# schematic.net
KiCad netlist of a schematic drawn in Altium Designer
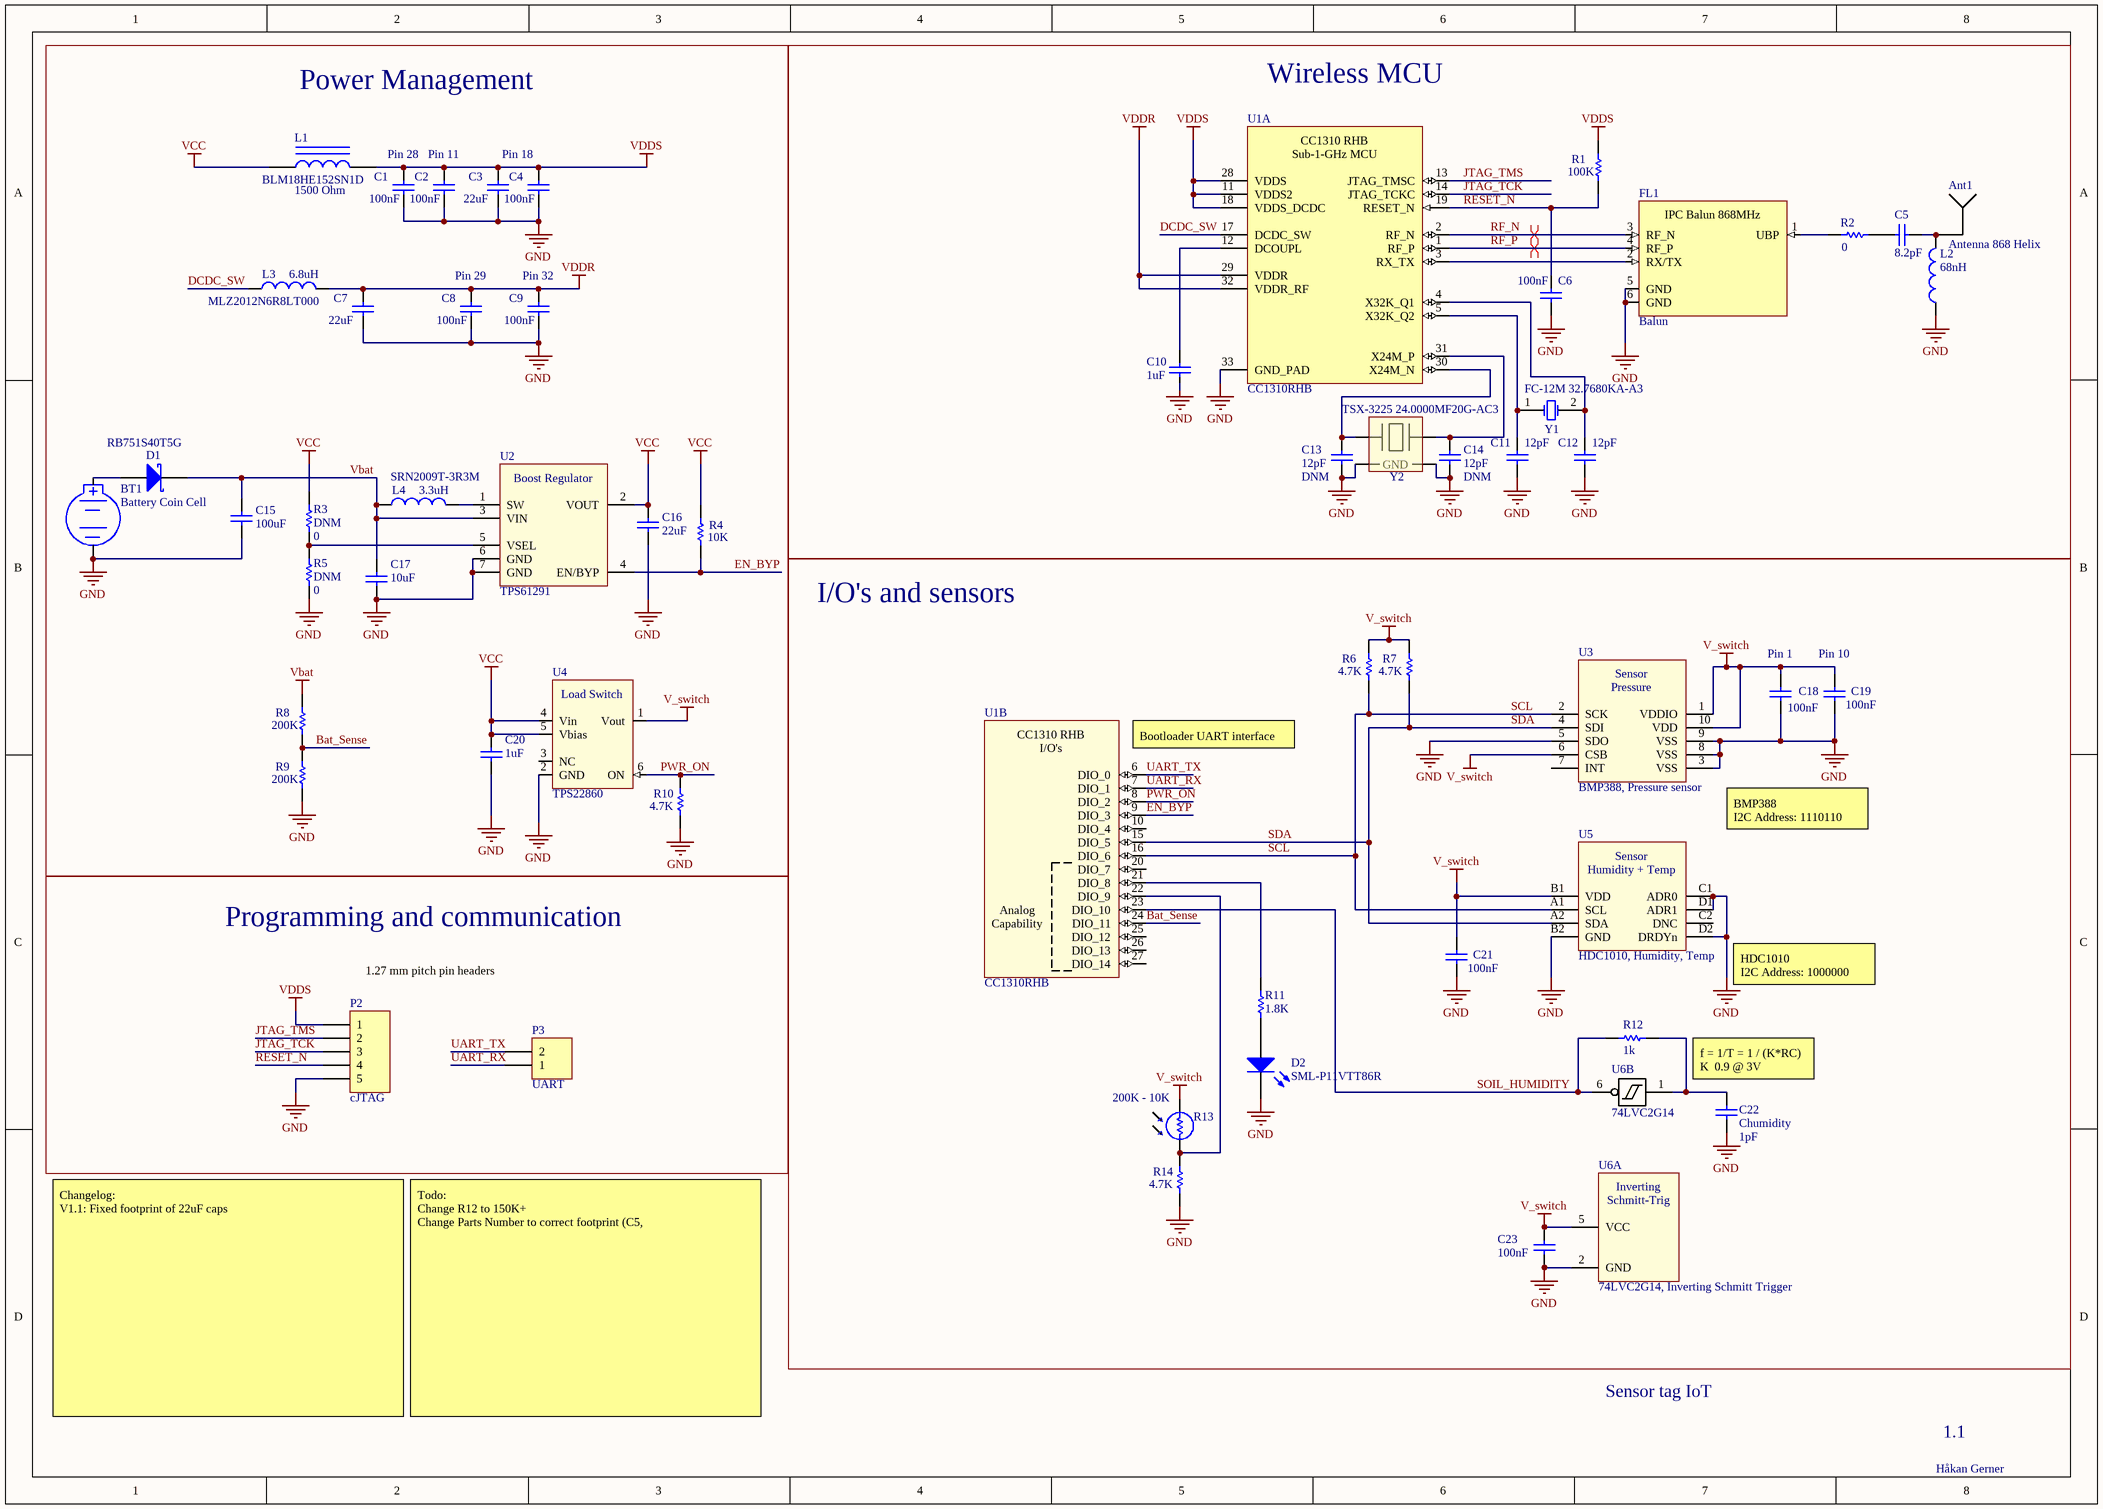
[diagram p0: schematic.SchDoc]

(export (version "E")
  (design (tool "Eeschema 10.0.6"))
  (components
    (comp (ref "Ant1")
      (value "Antenna 868 Helix")
      (footprint "Antenna_868_Helix")
      (libsource (lib "components") (part "Antenna 868 Helix"))
    )
    (comp (ref "BT1")
      (value "Battery Coin Cell")
      (footprint "S8421-45R")
      (fields (field (name "PART NUMBER") "S8421-45R"))
      (libsource (lib "components") (part "Battery Coin Cell"))
    )
    (comp (ref "C1")
      (value "100nF")
      (footprint "0402 (CAP)")
      (description "Capacitor")
      (fields
        (field (name "PART NUMBER") "GCM155R71C104KA55J")
        (field (name "Comment") "Cap")
        (field (name "PUBLISHER") "Altium Limited")
      )
      (libsource (lib "Miscellaneous Devices") (part "Cap"))
    )
    (comp (ref "C2")
      (value "100nF")
      (footprint "0402 (CAP)")
      (description "Capacitor")
      (fields
        (field (name "PART NUMBER") "GCM155R71C104KA55J")
        (field (name "Comment") "Cap")
        (field (name "PUBLISHER") "Altium Limited")
      )
      (libsource (lib "Miscellaneous Devices") (part "Cap"))
    )
    (comp (ref "C3")
      (value "22uF")
      (footprint "0603 (CAP)")
      (description "Capacitor")
      (fields
        (field (name "PART NUMBER") "GRM188R61A226ME15D")
        (field (name "Comment") "Cap")
        (field (name "PUBLISHER") "Altium Limited")
      )
      (libsource (lib "Miscellaneous Devices") (part "Cap"))
    )
    (comp (ref "C4")
      (value "100nF")
      (footprint "0402 (CAP)")
      (description "Capacitor")
      (fields
        (field (name "PART NUMBER") "GCM155R71C104KA55J")
        (field (name "Comment") "Cap")
        (field (name "PUBLISHER") "Altium Limited")
      )
      (libsource (lib "Miscellaneous Devices") (part "Cap"))
    )
    (comp (ref "C5")
      (value "8.2pF")
      (footprint "0402 (CAP)")
      (description "Capacitor")
      (fields
        (field (name "PART NUMBER") "250R05L8R2CV4T")
        (field (name "Comment") "Cap")
        (field (name "PUBLISHER") "Altium Limited")
      )
      (libsource (lib "Miscellaneous Devices") (part "Cap"))
    )
    (comp (ref "C6")
      (value "100nF")
      (footprint "0402 (CAP)")
      (description "Capacitor")
      (fields
        (field (name "PART NUMBER") "GCM155R71C104KA55J")
        (field (name "Comment") "Cap")
        (field (name "PUBLISHER") "Altium Limited")
      )
      (libsource (lib "Miscellaneous Devices") (part "Cap"))
    )
    (comp (ref "C7")
      (value "22uF")
      (footprint "0603 (CAP)")
      (description "Capacitor")
      (fields
        (field (name "PART NUMBER") "GRM188R61A226ME15D")
        (field (name "Comment") "Cap")
        (field (name "PUBLISHER") "Altium Limited")
      )
      (libsource (lib "Miscellaneous Devices") (part "Cap"))
    )
    (comp (ref "C8")
      (value "100nF")
      (footprint "0402 (CAP)")
      (description "Capacitor")
      (fields
        (field (name "PART NUMBER") "GCM155R71C104KA55J")
        (field (name "Comment") "Cap")
        (field (name "PUBLISHER") "Altium Limited")
      )
      (libsource (lib "Miscellaneous Devices") (part "Cap"))
    )
    (comp (ref "C9")
      (value "100nF")
      (footprint "0402 (CAP)")
      (description "Capacitor")
      (fields
        (field (name "PART NUMBER") "GCM155R71C104KA55J")
        (field (name "Comment") "Cap")
        (field (name "PUBLISHER") "Altium Limited")
      )
      (libsource (lib "Miscellaneous Devices") (part "Cap"))
    )
    (comp (ref "C10")
      (value "1uF")
      (footprint "0603 (CAP)")
      (description "Capacitor")
      (fields
        (field (name "PART NUMBER") "GCM188R71E105KA64D")
        (field (name "Comment") "Cap")
        (field (name "PUBLISHER") "Altium Limited")
      )
      (libsource (lib "Miscellaneous Devices") (part "Cap"))
    )
    (comp (ref "C11")
      (value "12pF")
      (footprint "0402 (CAP)")
      (description "Capacitor")
      (fields
        (field (name "PART NUMBER") "GCM1555C1H120JA16D")
        (field (name "Comment") "Cap")
        (field (name "PUBLISHER") "Altium Limited")
      )
      (libsource (lib "Miscellaneous Devices") (part "Cap"))
    )
    (comp (ref "C12")
      (value "12pF")
      (footprint "0402 (CAP)")
      (description "Capacitor")
      (fields
        (field (name "PART NUMBER") "GCM1555C1H120JA16D")
        (field (name "Comment") "Cap")
        (field (name "PUBLISHER") "Altium Limited")
      )
      (libsource (lib "Miscellaneous Devices") (part "Cap"))
    )
    (comp (ref "C13")
      (value "DNM")
      (footprint "0402 (CAP)")
      (description "Capacitor")
      (fields
        (field (name "ALTIUM_VALUE") "12pF")
        (field (name "PART NUMBER") "GCM1555C1H120JA16D")
        (field (name "PUBLISHER") "Altium Limited")
      )
      (libsource (lib "Miscellaneous Devices") (part "Cap"))
    )
    (comp (ref "C14")
      (value "DNM")
      (footprint "0402 (CAP)")
      (description "Capacitor")
      (fields
        (field (name "ALTIUM_VALUE") "12pF")
        (field (name "PART NUMBER") "GCM1555C1H120JA16D")
        (field (name "PUBLISHER") "Altium Limited")
      )
      (libsource (lib "Miscellaneous Devices") (part "Cap"))
    )
    (comp (ref "C15")
      (value "100uF")
      (footprint "1210 (CAP)")
      (description "Capacitor")
      (fields
        (field (name "PART NUMBER") "GCM155R71C104KA55J")
        (field (name "Comment") "GRM32EC70J107ME15L")
        (field (name "PUBLISHER") "Altium Limited")
      )
      (libsource (lib "Miscellaneous Devices") (part "Cap"))
    )
    (comp (ref "C16")
      (value "22uF")
      (footprint "0805 (CAP)")
      (description "Capacitor")
      (fields
        (field (name "PART NUMBER") "GRM21BD71A226ME44L")
        (field (name "Comment") "Cap")
        (field (name "PUBLISHER") "Altium Limited")
      )
      (libsource (lib "Miscellaneous Devices") (part "Cap"))
    )
    (comp (ref "C17")
      (value "10uF")
      (footprint "0805 (CAP)")
      (description "Capacitor")
      (fields
        (field (name "PART NUMBER") "GRM21BC71C106KE11L")
        (field (name "Comment") "Cap")
        (field (name "PUBLISHER") "Altium Limited")
      )
      (libsource (lib "Miscellaneous Devices") (part "Cap"))
    )
    (comp (ref "C18")
      (value "100nF")
      (footprint "0402 (CAP)")
      (description "Capacitor")
      (fields
        (field (name "PART NUMBER") "GCM155R71C104KA55J")
        (field (name "Comment") "Cap")
        (field (name "PUBLISHER") "Altium Limited")
      )
      (libsource (lib "Miscellaneous Devices") (part "Cap"))
    )
    (comp (ref "C19")
      (value "100nF")
      (footprint "0402 (CAP)")
      (description "Capacitor")
      (fields
        (field (name "PART NUMBER") "GCM155R71C104KA55J")
        (field (name "Comment") "Cap")
        (field (name "PUBLISHER") "Altium Limited")
      )
      (libsource (lib "Miscellaneous Devices") (part "Cap"))
    )
    (comp (ref "C20")
      (value "1uF")
      (footprint "0603 (CAP)")
      (description "Capacitor")
      (fields
        (field (name "PART NUMBER") "GCM188R71E105KA64D")
        (field (name "Comment") "Cap")
        (field (name "PUBLISHER") "Altium Limited")
      )
      (libsource (lib "Miscellaneous Devices") (part "Cap"))
    )
    (comp (ref "C21")
      (value "100nF")
      (footprint "0402 (CAP)")
      (description "Capacitor")
      (fields
        (field (name "PART NUMBER") "GCM155R71C104KA55J")
        (field (name "Comment") "Cap")
        (field (name "PUBLISHER") "Altium Limited")
      )
      (libsource (lib "Miscellaneous Devices") (part "Cap"))
    )
    (comp (ref "C22")
      (value "Chumidity")
      (footprint "Soil_Cap")
      (description "Capacitor")
      (fields (field (name "ALTIUM_VALUE") "1pF") (field (name "PUBLISHER") "Altium Limited"))
      (libsource (lib "Miscellaneous Devices") (part "Cap"))
    )
    (comp (ref "C23")
      (value "100nF")
      (footprint "0402 (CAP)")
      (description "Capacitor")
      (fields
        (field (name "PART NUMBER") "GCM155R71C104KA55J")
        (field (name "Comment") "Cap")
        (field (name "PUBLISHER") "Altium Limited")
      )
      (libsource (lib "Miscellaneous Devices") (part "Cap"))
    )
    (comp (ref "D1")
      (value "RB751S40T5G")
      (footprint "SOD-523")
      (description "Schottky Diode")
      (fields (field (name "PUBLISHER") "Altium Limited"))
      (libsource (lib "Miscellaneous Devices") (part "D Schottky"))
    )
    (comp (ref "D2")
      (value "SML-P11VTT86R")
      (footprint "0402 (RES)")
      (description "Typical RED, GREEN, YELLOW, AMBER GaAs LED")
      (fields (field (name "PUBLISHER") "Altium Limited"))
      (libsource (lib "Miscellaneous Devices") (part "LED2"))
    )
    (comp (ref "FL1")
      (value "Balun")
      (footprint "0850BM14E0016")
      (fields (field (name "PART NUMBER") "0850BM14E0016T"))
      (libsource (lib "components") (part "0850BM14E0016"))
    )
    (comp (ref "L1")
      (value "BLM18HE152SN1D")
      (footprint "0603 (IND)")
      (description "Magnetic-Core Inductor")
      (fields (field (name "ALTIUM_VALUE") "1500 Ohm") (field (name "PUBLISHER") "Altium Limited"))
      (libsource (lib "Miscellaneous Devices") (part "Inductor Iron"))
    )
    (comp (ref "L2")
      (value "68nH")
      (footprint "0603 (IND)")
      (description "Inductor")
      (fields (field (name "PART NUMBER") "PE-0603CD680GTT") (field (name "PUBLISHER") "Altium Limited"))
      (libsource (lib "") (part "Inductor_1"))
    )
    (comp (ref "L3")
      (value "MLZ2012N6R8LT000")
      (footprint "0805 (IND)")
      (description "Inductor")
      (fields (field (name "ALTIUM_VALUE") "6.8uH") (field (name "PUBLISHER") "Altium Limited"))
      (libsource (lib "Miscellaneous Devices") (part "Inductor"))
    )
    (comp (ref "L4")
      (value "3.3uH")
      (footprint "SRN2009T")
      (description "Inductor")
      (fields (field (name "PART NUMBER") "SRN2009T-3R3M") (field (name "PUBLISHER") "Altium Limited"))
      (libsource (lib "Miscellaneous Devices") (part "Inductor"))
    )
    (comp (ref "P2")
      (value "cJTAG")
      (footprint "5pin-1.27")
      (description "Header, 5-Pin")
      (fields (field (name "PUBLISHER") "Altium Limited"))
      (libsource (lib "Miscellaneous Connectors") (part "Header 5"))
    )
    (comp (ref "P3")
      (value "UART")
      (footprint "2pin-1.27")
      (description "Header, 2-Pin")
      (fields (field (name "PUBLISHER") "Altium Limited"))
      (libsource (lib "Miscellaneous Connectors") (part "Header 2"))
    )
    (comp (ref "R1")
      (value "100K")
      (footprint "0402 (RES)")
      (description "Resistor")
      (fields
        (field (name "PART NUMBER") "CRCW0402100KFKED")
        (field (name "Comment") "Res1")
        (field (name "PUBLISHER") "Altium Limited")
      )
      (libsource (lib "Miscellaneous Devices") (part "Res1"))
    )
    (comp (ref "R2")
      (value "0")
      (footprint "0402 (RES)")
      (description "Resistor")
      (fields (field (name "PART NUMBER") "ERJ-2GE0R00X") (field (name "PUBLISHER") "Altium Limited"))
      (libsource (lib "Miscellaneous Devices") (part "Res1"))
    )
    (comp (ref "R3")
      (value "DNM")
      (footprint "0402 (RES)")
      (description "Resistor")
      (fields
        (field (name "ALTIUM_VALUE") "0")
        (field (name "PART NUMBER") "ERJ-2GE0R00X")
        (field (name "PUBLISHER") "Altium Limited")
      )
      (libsource (lib "Miscellaneous Devices") (part "Res1"))
    )
    (comp (ref "R4")
      (value "10K")
      (footprint "0402 (RES)")
      (description "Resistor")
      (fields
        (field (name "PART NUMBER") "CRCW040210K0JNEDC")
        (field (name "Comment") "Res1")
        (field (name "PUBLISHER") "Altium Limited")
      )
      (libsource (lib "Miscellaneous Devices") (part "Res1"))
    )
    (comp (ref "R5")
      (value "DNM")
      (footprint "0402 (RES)")
      (description "Resistor")
      (fields
        (field (name "ALTIUM_VALUE") "0")
        (field (name "PART NUMBER") "ERJ-2GE0R00X")
        (field (name "PUBLISHER") "Altium Limited")
      )
      (libsource (lib "Miscellaneous Devices") (part "Res1"))
    )
    (comp (ref "R6")
      (value "4.7K")
      (footprint "0402 (RES)")
      (description "Resistor")
      (fields
        (field (name "PART NUMBER") "CRCW04024K70FKEDC")
        (field (name "Comment") "Res1")
        (field (name "PUBLISHER") "Altium Limited")
      )
      (libsource (lib "Miscellaneous Devices") (part "Res1"))
    )
    (comp (ref "R7")
      (value "4.7K")
      (footprint "0402 (RES)")
      (description "Resistor")
      (fields
        (field (name "PART NUMBER") "CRCW04024K70FKEDC")
        (field (name "Comment") "Res1")
        (field (name "PUBLISHER") "Altium Limited")
      )
      (libsource (lib "Miscellaneous Devices") (part "Res1"))
    )
    (comp (ref "R8")
      (value "200K")
      (footprint "0402 (RES)")
      (description "Resistor")
      (fields
        (field (name "PART NUMBER") "CRG0402F4K7")
        (field (name "Comment") "Res1")
        (field (name "PUBLISHER") "Altium Limited")
      )
      (libsource (lib "Miscellaneous Devices") (part "Res1"))
    )
    (comp (ref "R9")
      (value "200K")
      (footprint "0402 (RES)")
      (description "Resistor")
      (fields
        (field (name "PART NUMBER") "CRG0402F4K7")
        (field (name "Comment") "Res1")
        (field (name "PUBLISHER") "Altium Limited")
      )
      (libsource (lib "Miscellaneous Devices") (part "Res1"))
    )
    (comp (ref "R10")
      (value "4.7K")
      (footprint "0402 (RES)")
      (description "Resistor")
      (fields
        (field (name "PART NUMBER") "CRCW04024K70FKEDC")
        (field (name "Comment") "Res1")
        (field (name "PUBLISHER") "Altium Limited")
      )
      (libsource (lib "Miscellaneous Devices") (part "Res1"))
    )
    (comp (ref "R11")
      (value "1.8K")
      (footprint "0402 (RES)")
      (description "Resistor")
      (fields
        (field (name "PART NUMBER") "ERJ-2RKF1801X")
        (field (name "Comment") "Res1")
        (field (name "PUBLISHER") "Altium Limited")
      )
      (libsource (lib "Miscellaneous Devices") (part "Res1"))
    )
    (comp (ref "R12")
      (value "1k")
      (footprint "0402 (RES)")
      (description "Resistor")
      (fields
        (field (name "PART NUMBER") "RMCF0402ZT0R00CT-ND")
        (field (name "Comment") "Rcharge")
        (field (name "PUBLISHER") "Altium Limited")
      )
      (libsource (lib "Miscellaneous Devices") (part "Res1"))
    )
    (comp (ref "R13")
      (value "200K - 10K")
      (footprint "Photoresistor")
      (libsource (lib "components") (part "Photo Resistor"))
    )
    (comp (ref "R14")
      (value "4.7K")
      (footprint "0402 (RES)")
      (description "Resistor")
      (fields
        (field (name "PART NUMBER") "CRCW04024K70FKEDC")
        (field (name "Comment") "Res1")
        (field (name "PUBLISHER") "Altium Limited")
      )
      (libsource (lib "Miscellaneous Devices") (part "Res1"))
    )
    (comp (ref "U1")
      (value "CC1310RHB")
      (footprint "VQFN-32_5x5")
      (fields (field (name "PART NUMBER") "CC1310F128RHBT"))
      (libsource (lib "components") (part "CC1310RHB"))
    )
    (comp (ref "U2")
      (value "TPS61291")
      (footprint "TPS61291")
      (fields (field (name "PART NUMBER") "TPS61291DRVR"))
      (libsource (lib "components") (part "TPS61291"))
    )
    (comp (ref "U3")
      (value "BMP388, Pressure sensor")
      (footprint "BMP388")
      (fields (field (name "PART NUMBER") "BMP388"))
      (libsource (lib "components") (part "BMP388"))
    )
    (comp (ref "U4")
      (value "TPS22860")
      (footprint "SOT23-5")
      (fields (field (name "PART NUMBER") "TPS22860DBVR"))
      (libsource (lib "components") (part "TPS22860"))
    )
    (comp (ref "U5")
      (value "HDC1010, Humidity, Temp")
      (footprint "HDC1010")
      (fields (field (name "PART NUMBER") "HDC1010YPAR"))
      (libsource (lib "components") (part "HDC1010"))
    )
    (comp (ref "U6")
      (value "74LVC2G14, Inverting Schmitt Trigger")
      (footprint "74LVC2G14")
      (fields (field (name "PART NUMBER") "74LVC2G14GV,125"))
      (libsource (lib "components") (part "74LVC2G14"))
    )
    (comp (ref "Y1")
      (value "FC-12M 32.7680KA-A3")
      (footprint "FC-12M 32.7680KA-A3")
      (description "Crystal Oscillator")
      (fields (field (name "PUBLISHER") "Altium Limited"))
      (libsource (lib "Miscellaneous Devices") (part "XTAL"))
    )
    (comp (ref "Y2")
      (value "TSX-3225 24.0000MF20G-AC3")
      (footprint "TSX-3225 24.0000MF20G-AC3")
      (libsource (lib "components") (part "Crystal"))
    )
  )
  (nets
    (net (code "1") (name "/Bat_Sense") (class "Default")
      (node (ref "R8") (pin "1") (pinfunction "1_1") (pintype "passive"))
      (node (ref "R9") (pin "2") (pinfunction "2_2") (pintype "passive"))
      (node (ref "U1") (pin "24") (pinfunction "DIO_11_24") (pintype "bidirectional"))
    )
    (net (code "2") (name "/DCDC_SW") (class "Default")
      (node (ref "L3") (pin "1") (pinfunction "1_1") (pintype "passive"))
      (node (ref "U1") (pin "17") (pinfunction "DCDC_SW_17") (pintype "power_in"))
    )
    (net (code "3") (name "/EN_BYP") (class "Default")
      (node (ref "R4") (pin "2") (pinfunction "2_2") (pintype "passive"))
      (node (ref "U1") (pin "9") (pinfunction "DIO_3_9") (pintype "bidirectional"))
      (node (ref "U2") (pin "4") (pinfunction "EN/BYP_4") (pintype "passive"))
    )
    (net (code "4") (name "/JTAG_TCK") (class "Default")
      (node (ref "P2") (pin "3") (pinfunction "3_3") (pintype "passive"))
      (node (ref "U1") (pin "14") (pinfunction "JTAG_TCKC_14") (pintype "bidirectional"))
    )
    (net (code "5") (name "/JTAG_TMS") (class "Default")
      (node (ref "P2") (pin "2") (pinfunction "2_2") (pintype "passive"))
      (node (ref "U1") (pin "13") (pinfunction "JTAG_TMSC_13") (pintype "bidirectional"))
    )
    (net (code "6") (name "/PWR_ON") (class "Default")
      (node (ref "R10") (pin "2") (pinfunction "2_2") (pintype "passive"))
      (node (ref "U1") (pin "8") (pinfunction "DIO_2_8") (pintype "bidirectional"))
      (node (ref "U4") (pin "6") (pinfunction "ON_6") (pintype "input"))
    )
    (net (code "7") (name "/RESET_N") (class "Default")
      (node (ref "C6") (pin "1") (pinfunction "1_1") (pintype "passive"))
      (node (ref "P2") (pin "4") (pinfunction "4_4") (pintype "passive"))
      (node (ref "R1") (pin "1") (pinfunction "1_1") (pintype "passive"))
      (node (ref "U1") (pin "19") (pinfunction "RESET_N_19") (pintype "input"))
    )
    (net (code "8") (name "/RF_N") (class "Default")
      (node (ref "FL1") (pin "3") (pinfunction "RF_N_3") (pintype "input"))
      (node (ref "U1") (pin "2") (pinfunction "RF_N_2") (pintype "bidirectional"))
    )
    (net (code "9") (name "/RF_P") (class "Default")
      (node (ref "FL1") (pin "4") (pinfunction "RF_P_4") (pintype "input"))
      (node (ref "U1") (pin "1") (pinfunction "RF_P_1") (pintype "bidirectional"))
    )
    (net (code "10") (name "/SCL") (class "Default")
      (node (ref "R6") (pin "1") (pinfunction "1_1") (pintype "passive"))
      (node (ref "U1") (pin "16") (pinfunction "DIO_6_16") (pintype "bidirectional"))
      (node (ref "U3") (pin "2") (pinfunction "SCK_2") (pintype "passive"))
      (node (ref "U5") (pin "A1") (pinfunction "SCL_A1") (pintype "passive"))
    )
    (net (code "11") (name "/SDA") (class "Default")
      (node (ref "R7") (pin "1") (pinfunction "1_1") (pintype "passive"))
      (node (ref "U1") (pin "15") (pinfunction "DIO_5_15") (pintype "bidirectional"))
      (node (ref "U3") (pin "4") (pinfunction "SDI_4") (pintype "passive"))
      (node (ref "U5") (pin "A2") (pinfunction "SDA_A2") (pintype "passive"))
    )
    (net (code "12") (name "/SOIL_HUMIDITY") (class "Default")
      (node (ref "R12") (pin "2") (pinfunction "2_2") (pintype "passive"))
      (node (ref "U1") (pin "23") (pinfunction "DIO_10_23") (pintype "bidirectional"))
      (node (ref "U6") (pin "6") (pinfunction "1Y_6") (pintype "passive"))
    )
    (net (code "13") (name "/UART_RX") (class "Default")
      (node (ref "P3") (pin "1") (pinfunction "1_1") (pintype "passive"))
      (node (ref "U1") (pin "7") (pinfunction "DIO_1_7") (pintype "bidirectional"))
    )
    (net (code "14") (name "/UART_TX") (class "Default")
      (node (ref "P3") (pin "2") (pinfunction "2_2") (pintype "passive"))
      (node (ref "U1") (pin "6") (pinfunction "DIO_0_6") (pintype "bidirectional"))
    )
    (net (code "15") (name "GND") (class "Default")
      (node (ref "BT1") (pin "2") (pinfunction "Negative_2") (pintype "passive"))
      (node (ref "C1") (pin "1") (pinfunction "1_1") (pintype "passive"))
      (node (ref "C10") (pin "1") (pinfunction "1_1") (pintype "passive"))
      (node (ref "C11") (pin "1") (pinfunction "1_1") (pintype "passive"))
      (node (ref "C12") (pin "1") (pinfunction "1_1") (pintype "passive"))
      (node (ref "C13") (pin "1") (pinfunction "1_1") (pintype "passive"))
      (node (ref "C14") (pin "1") (pinfunction "1_1") (pintype "passive"))
      (node (ref "C15") (pin "1") (pinfunction "1_1") (pintype "passive"))
      (node (ref "C16") (pin "1") (pinfunction "1_1") (pintype "passive"))
      (node (ref "C17") (pin "1") (pinfunction "1_1") (pintype "passive"))
      (node (ref "C18") (pin "1") (pinfunction "1_1") (pintype "passive"))
      (node (ref "C19") (pin "1") (pinfunction "1_1") (pintype "passive"))
      (node (ref "C2") (pin "1") (pinfunction "1_1") (pintype "passive"))
      (node (ref "C20") (pin "1") (pinfunction "1_1") (pintype "passive"))
      (node (ref "C21") (pin "1") (pinfunction "1_1") (pintype "passive"))
      (node (ref "C22") (pin "2") (pinfunction "2_2") (pintype "passive"))
      (node (ref "C23") (pin "1") (pinfunction "1_1") (pintype "passive"))
      (node (ref "C3") (pin "1") (pinfunction "1_1") (pintype "passive"))
      (node (ref "C4") (pin "1") (pinfunction "1_1") (pintype "passive"))
      (node (ref "C6") (pin "2") (pinfunction "2_2") (pintype "passive"))
      (node (ref "C7") (pin "1") (pinfunction "1_1") (pintype "passive"))
      (node (ref "C8") (pin "1") (pinfunction "1_1") (pintype "passive"))
      (node (ref "C9") (pin "1") (pinfunction "1_1") (pintype "passive"))
      (node (ref "D2") (pin "2") (pinfunction "K_2") (pintype "passive"))
      (node (ref "FL1") (pin "5") (pinfunction "GND_5") (pintype "power_in"))
      (node (ref "FL1") (pin "6") (pinfunction "GND_6") (pintype "power_in"))
      (node (ref "L2") (pin "2") (pinfunction "2_2") (pintype "passive"))
      (node (ref "P2") (pin "5") (pinfunction "5_5") (pintype "passive"))
      (node (ref "R10") (pin "1") (pinfunction "1_1") (pintype "passive"))
      (node (ref "R14") (pin "1") (pinfunction "1_1") (pintype "passive"))
      (node (ref "R5") (pin "2") (pinfunction "2_2") (pintype "passive"))
      (node (ref "R9") (pin "1") (pinfunction "1_1") (pintype "passive"))
      (node (ref "U1") (pin "33") (pinfunction "GND_PAD_33") (pintype "passive"))
      (node (ref "U2") (pin "6") (pinfunction "GND_6") (pintype "passive"))
      (node (ref "U2") (pin "7") (pinfunction "GND_7") (pintype "passive"))
      (node (ref "U3") (pin "3") (pinfunction "VSS_3") (pintype "passive"))
      (node (ref "U3") (pin "5") (pinfunction "SDO_5") (pintype "passive"))
      (node (ref "U3") (pin "8") (pinfunction "VSS_8") (pintype "passive"))
      (node (ref "U3") (pin "9") (pinfunction "VSS_9") (pintype "passive"))
      (node (ref "U4") (pin "2") (pinfunction "GND_2") (pintype "power_in"))
      (node (ref "U5") (pin "B2") (pinfunction "GND_B2") (pintype "passive"))
      (node (ref "U5") (pin "C1") (pinfunction "ADR0_C1") (pintype "passive"))
      (node (ref "U5") (pin "D1") (pinfunction "ADR1_D1") (pintype "passive"))
      (node (ref "U5") (pin "D2") (pinfunction "DRDYn_D2") (pintype "passive"))
      (node (ref "U6") (pin "2") (pinfunction "GND_2") (pintype "passive"))
      (node (ref "Y2") (pin "2") (pinfunction "ON_2") (pintype "passive"))
      (node (ref "Y2") (pin "4") (pinfunction "ON_4") (pintype "passive"))
    )
    (net (code "16") (name "Net-(Ant1-0)") (class "Default")
      (node (ref "Ant1") (pin "1") (pinfunction "0_1") (pintype "passive"))
      (node (ref "C5") (pin "2") (pinfunction "2_2") (pintype "passive"))
      (node (ref "L2") (pin "1") (pinfunction "1_1") (pintype "passive"))
    )
    (net (code "17") (name "Net-(BT1-Positive)") (class "Default")
      (node (ref "BT1") (pin "1") (pinfunction "Positive_1") (pintype "passive"))
      (node (ref "D1") (pin "1") (pinfunction "A_1") (pintype "passive"))
    )
    (net (code "18") (name "Net-(C5-Pad1)") (class "Default")
      (node (ref "C5") (pin "1") (pinfunction "1_1") (pintype "passive"))
      (node (ref "R2") (pin "2") (pinfunction "2_2") (pintype "passive"))
    )
    (net (code "19") (name "Net-(D2-A)") (class "Default")
      (node (ref "D2") (pin "1") (pinfunction "A_1") (pintype "passive"))
      (node (ref "R11") (pin "2") (pinfunction "2_2") (pintype "passive"))
    )
    (net (code "20") (name "Net-(FL1-RX{slash}TX)") (class "Default")
      (node (ref "FL1") (pin "2") (pinfunction "RX/TX_2") (pintype "input"))
      (node (ref "U1") (pin "3") (pinfunction "RX_TX_3") (pintype "bidirectional"))
    )
    (net (code "21") (name "Net-(FL1-UBP)") (class "Default")
      (node (ref "FL1") (pin "1") (pinfunction "UBP_1") (pintype "input"))
      (node (ref "R2") (pin "1") (pinfunction "1_1") (pintype "passive"))
    )
    (net (code "22") (name "Net-(U1A-DCOUPL)") (class "Default")
      (node (ref "C10") (pin "2") (pinfunction "2_2") (pintype "passive"))
      (node (ref "U1") (pin "12") (pinfunction "DCOUPL_12") (pintype "power_in"))
    )
    (net (code "23") (name "Net-(U1A-X24M_N)") (class "Default")
      (node (ref "C13") (pin "2") (pinfunction "2_2") (pintype "passive"))
      (node (ref "U1") (pin "30") (pinfunction "X24M_N_30") (pintype "bidirectional"))
      (node (ref "Y2") (pin "1") (pinfunction "ON_1") (pintype "passive"))
    )
    (net (code "24") (name "Net-(U1A-X24M_P)") (class "Default")
      (node (ref "C14") (pin "2") (pinfunction "2_2") (pintype "passive"))
      (node (ref "U1") (pin "31") (pinfunction "X24M_P_31") (pintype "bidirectional"))
      (node (ref "Y2") (pin "3") (pinfunction "ON_3") (pintype "passive"))
    )
    (net (code "25") (name "Net-(U1A-X32K_Q1)") (class "Default")
      (node (ref "C12") (pin "2") (pinfunction "2_2") (pintype "passive"))
      (node (ref "U1") (pin "4") (pinfunction "X32K_Q1_4") (pintype "bidirectional"))
      (node (ref "Y1") (pin "2") (pinfunction "OSC2_2") (pintype "passive"))
    )
    (net (code "26") (name "Net-(U1A-X32K_Q2)") (class "Default")
      (node (ref "C11") (pin "2") (pinfunction "2_2") (pintype "passive"))
      (node (ref "U1") (pin "5") (pinfunction "X32K_Q2_5") (pintype "bidirectional"))
      (node (ref "Y1") (pin "1") (pinfunction "OSC1_1") (pintype "passive"))
    )
    (net (code "27") (name "Net-(U1B-DIO_8)") (class "Default")
      (node (ref "R11") (pin "1") (pinfunction "1_1") (pintype "passive"))
      (node (ref "U1") (pin "21") (pinfunction "DIO_8_21") (pintype "bidirectional"))
    )
    (net (code "28") (name "Net-(U1B-DIO_9)") (class "Default")
      (node (ref "R13") (pin "2") (pinfunction "2_2") (pintype "passive"))
      (node (ref "R14") (pin "2") (pinfunction "2_2") (pintype "passive"))
      (node (ref "U1") (pin "22") (pinfunction "DIO_9_22") (pintype "bidirectional"))
    )
    (net (code "29") (name "Net-(U2-SW)") (class "Default")
      (node (ref "L4") (pin "2") (pinfunction "2_2") (pintype "passive"))
      (node (ref "U2") (pin "1") (pinfunction "SW_1") (pintype "passive"))
    )
    (net (code "30") (name "Net-(U2-VSEL)") (class "Default")
      (node (ref "R3") (pin "2") (pinfunction "2_2") (pintype "passive"))
      (node (ref "R5") (pin "1") (pinfunction "1_1") (pintype "passive"))
      (node (ref "U2") (pin "5") (pinfunction "VSEL_5") (pintype "passive"))
    )
    (net (code "31") (name "Net-(U6B-1A)") (class "Default")
      (node (ref "C22") (pin "1") (pinfunction "1_1") (pintype "passive"))
      (node (ref "R12") (pin "1") (pinfunction "1_1") (pintype "passive"))
      (node (ref "U6") (pin "1") (pinfunction "1A_1") (pintype "passive"))
    )
    (net (code "32") (name "VCC") (class "Default")
      (node (ref "C16") (pin "2") (pinfunction "2_2") (pintype "passive"))
      (node (ref "C20") (pin "2") (pinfunction "2_2") (pintype "passive"))
      (node (ref "L1") (pin "1") (pinfunction "1_1") (pintype "passive"))
      (node (ref "R3") (pin "1") (pinfunction "1_1") (pintype "passive"))
      (node (ref "R4") (pin "1") (pinfunction "1_1") (pintype "passive"))
      (node (ref "U2") (pin "2") (pinfunction "VOUT_2") (pintype "passive"))
      (node (ref "U4") (pin "4") (pinfunction "Vin_4") (pintype "power_in"))
      (node (ref "U4") (pin "5") (pinfunction "Vbias_5") (pintype "power_in"))
    )
    (net (code "33") (name "VDDR") (class "Default")
      (node (ref "C7") (pin "2") (pinfunction "2_2") (pintype "passive"))
      (node (ref "C8") (pin "2") (pinfunction "2_2") (pintype "passive"))
      (node (ref "C9") (pin "2") (pinfunction "2_2") (pintype "passive"))
      (node (ref "L3") (pin "2") (pinfunction "2_2") (pintype "passive"))
      (node (ref "U1") (pin "29") (pinfunction "VDDR_29") (pintype "power_in"))
      (node (ref "U1") (pin "32") (pinfunction "VDDR_RF_32") (pintype "power_in"))
    )
    (net (code "34") (name "VDDS") (class "Default")
      (node (ref "C1") (pin "2") (pinfunction "2_2") (pintype "passive"))
      (node (ref "C2") (pin "2") (pinfunction "2_2") (pintype "passive"))
      (node (ref "C3") (pin "2") (pinfunction "2_2") (pintype "passive"))
      (node (ref "C4") (pin "2") (pinfunction "2_2") (pintype "passive"))
      (node (ref "L1") (pin "2") (pinfunction "2_2") (pintype "passive"))
      (node (ref "P2") (pin "1") (pinfunction "1_1") (pintype "passive"))
      (node (ref "R1") (pin "2") (pinfunction "2_2") (pintype "passive"))
      (node (ref "U1") (pin "11") (pinfunction "VDDS2_11") (pintype "power_in"))
      (node (ref "U1") (pin "18") (pinfunction "VDDS_DCDC_18") (pintype "power_in"))
      (node (ref "U1") (pin "28") (pinfunction "VDDS_28") (pintype "power_in"))
    )
    (net (code "35") (name "V_switch") (class "Default")
      (node (ref "C18") (pin "2") (pinfunction "2_2") (pintype "passive"))
      (node (ref "C19") (pin "2") (pinfunction "2_2") (pintype "passive"))
      (node (ref "C21") (pin "2") (pinfunction "2_2") (pintype "passive"))
      (node (ref "C23") (pin "2") (pinfunction "2_2") (pintype "passive"))
      (node (ref "R13") (pin "1") (pinfunction "1_1") (pintype "passive"))
      (node (ref "R6") (pin "2") (pinfunction "2_2") (pintype "passive"))
      (node (ref "R7") (pin "2") (pinfunction "2_2") (pintype "passive"))
      (node (ref "U3") (pin "1") (pinfunction "VDDIO_1") (pintype "passive"))
      (node (ref "U3") (pin "10") (pinfunction "VDD_10") (pintype "passive"))
      (node (ref "U3") (pin "6") (pinfunction "CSB_6") (pintype "passive"))
      (node (ref "U4") (pin "1") (pinfunction "Vout_1") (pintype "power_in"))
      (node (ref "U5") (pin "B1") (pinfunction "VDD_B1") (pintype "passive"))
      (node (ref "U6") (pin "5") (pinfunction "VCC_5") (pintype "passive"))
    )
    (net (code "36") (name "Vbat") (class "Default")
      (node (ref "C15") (pin "2") (pinfunction "2_2") (pintype "passive"))
      (node (ref "C17") (pin "2") (pinfunction "2_2") (pintype "passive"))
      (node (ref "D1") (pin "2") (pinfunction "K_2") (pintype "passive"))
      (node (ref "L4") (pin "1") (pinfunction "1_1") (pintype "passive"))
      (node (ref "R8") (pin "2") (pinfunction "2_2") (pintype "passive"))
      (node (ref "U2") (pin "3") (pinfunction "VIN_3") (pintype "passive"))
    )
    (net (code "37") (name "unconnected-(U1B-DIO_4-Pad10)") (class "Default")
      (node (ref "U1") (pin "10") (pinfunction "DIO_4_10") (pintype "bidirectional"))
    )
    (net (code "38") (name "unconnected-(U1B-DIO_7-Pad20)") (class "Default")
      (node (ref "U1") (pin "20") (pinfunction "DIO_7_20") (pintype "bidirectional"))
    )
    (net (code "39") (name "unconnected-(U1B-DIO_12-Pad25)") (class "Default")
      (node (ref "U1") (pin "25") (pinfunction "DIO_12_25") (pintype "bidirectional"))
    )
    (net (code "40") (name "unconnected-(U1B-DIO_13-Pad26)") (class "Default")
      (node (ref "U1") (pin "26") (pinfunction "DIO_13_26") (pintype "bidirectional"))
    )
    (net (code "41") (name "unconnected-(U1B-DIO_14-Pad27)") (class "Default")
      (node (ref "U1") (pin "27") (pinfunction "DIO_14_27") (pintype "bidirectional"))
    )
    (net (code "42") (name "unconnected-(U3-INT-Pad7)") (class "Default")
      (node (ref "U3") (pin "7") (pinfunction "INT_7") (pintype "passive"))
    )
    (net (code "43") (name "unconnected-(U4-NC-Pad3)") (class "Default")
      (node (ref "U4") (pin "3") (pinfunction "NC_3") (pintype "passive"))
    )
    (net (code "44") (name "unconnected-(U5-DNC-PadC2)") (class "Default")
      (node (ref "U5") (pin "C2") (pinfunction "DNC_C2") (pintype "passive"))
    )
  )
)
